# ButtonMatrix.net
KiCad netlist of a schematic drawn in EAGLE
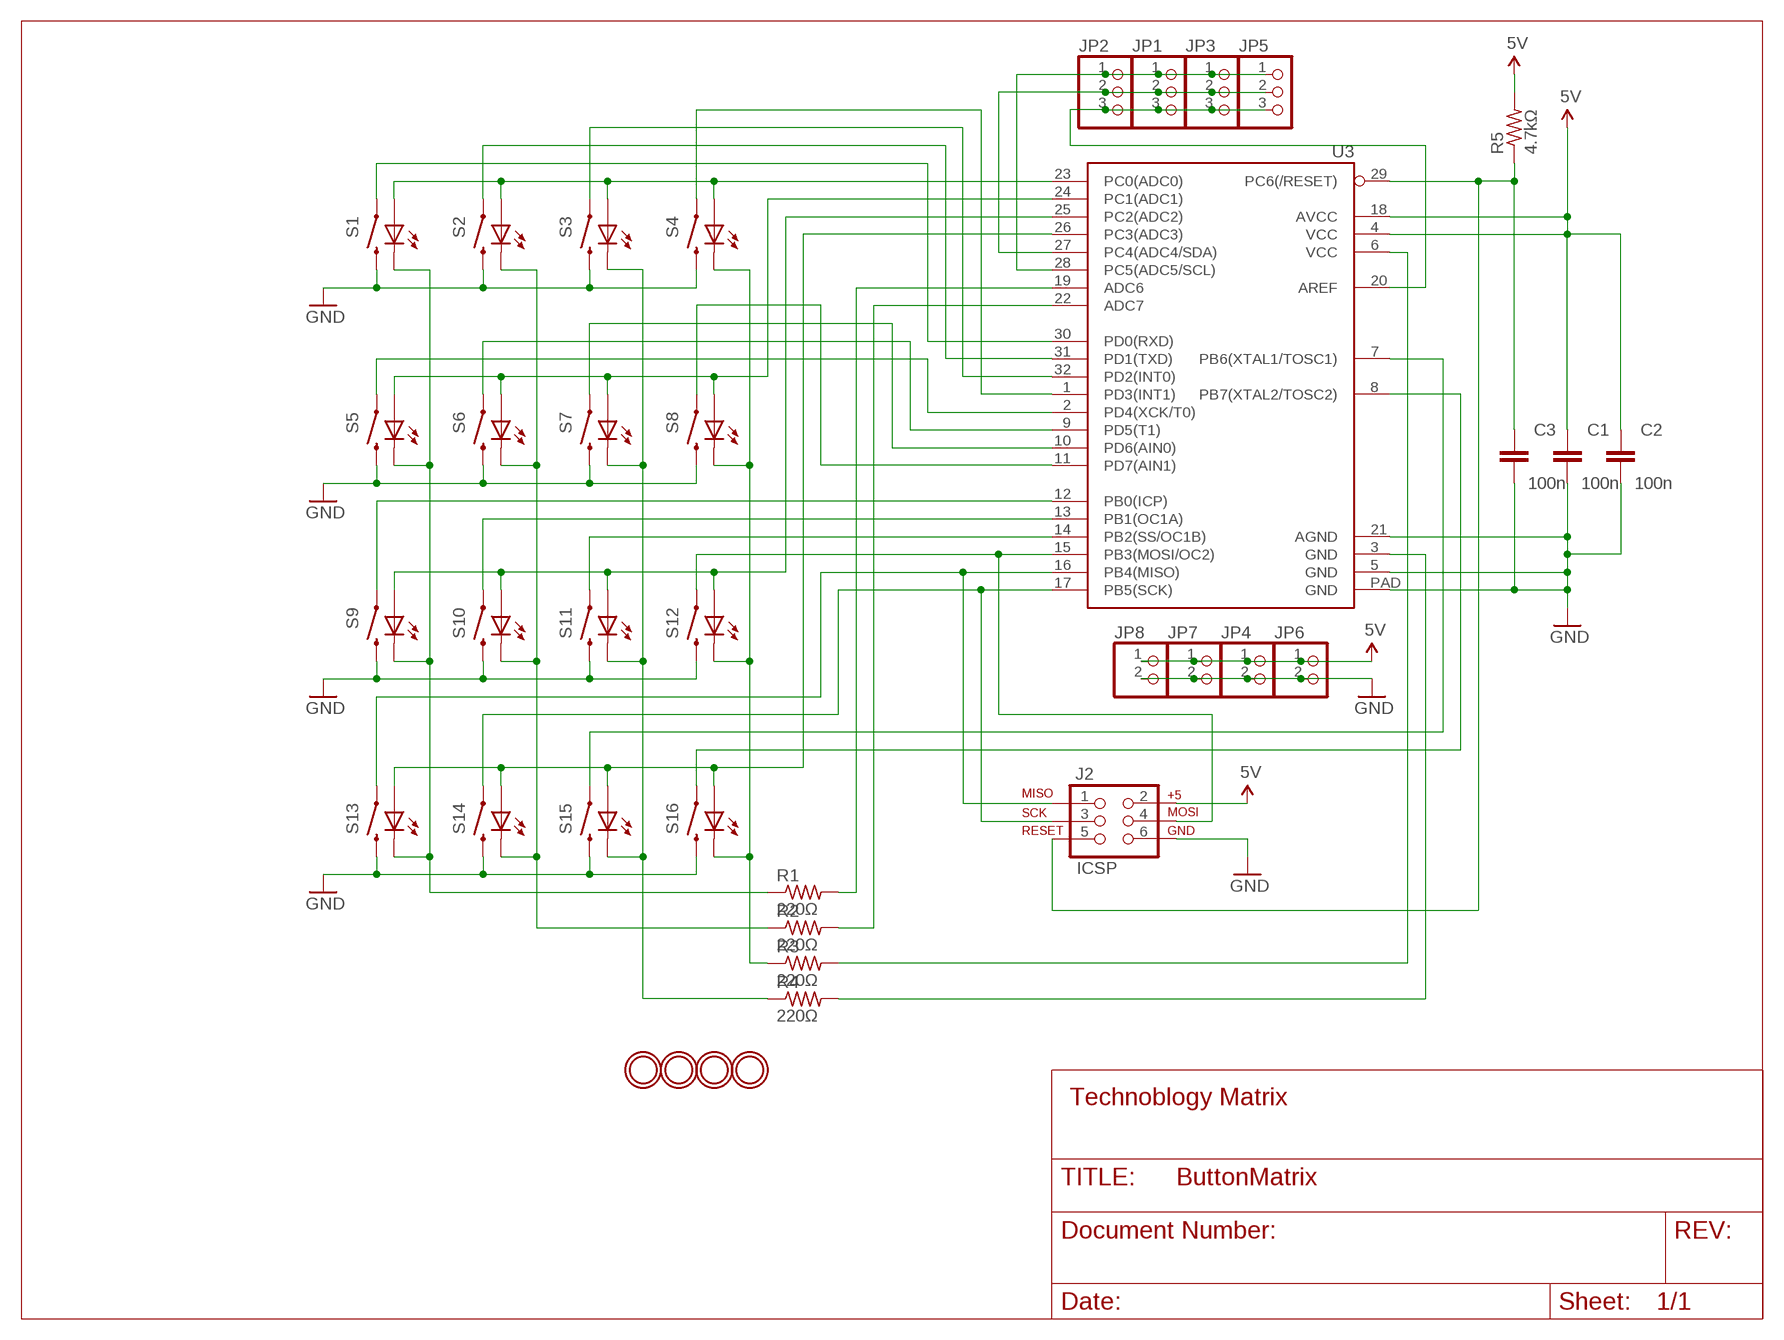
[diagram p0: schematic, sheet 1]

(export (version "E")
  (design (tool "Eeschema 10.0.6"))
  (components
    (comp (ref "C1")
      (value "100n")
      (footprint "eagle-import:0603-CAP")
      (libsource (lib "eagle-import") (part "CAP0603-CAP"))
    )
    (comp (ref "C2")
      (value "100n")
      (footprint "eagle-import:0603-CAP")
      (libsource (lib "eagle-import") (part "CAP0603-CAP"))
    )
    (comp (ref "C3")
      (value "100n")
      (footprint "eagle-import:0603-CAP")
      (libsource (lib "eagle-import") (part "CAP0603-CAP"))
    )
    (comp (ref "J2")
      (value "ICSP")
      (footprint "eagle-import:2X3")
      (libsource (lib "eagle-import") (part "AVR_SPI_PRG_6PTH"))
    )
    (comp (ref "JP1")
      (value "HEADER-1X3EDGESMT")
      (footprint "eagle-import:1X03_EDGESMT")
      (libsource (lib "eagle-import") (part "HEADER-1X3EDGESMT"))
    )
    (comp (ref "JP2")
      (value "HEADER-1X3EDGESMT")
      (footprint "eagle-import:1X03_EDGESMT")
      (libsource (lib "eagle-import") (part "HEADER-1X3EDGESMT"))
    )
    (comp (ref "JP3")
      (value "HEADER-1X3EDGESMT")
      (footprint "eagle-import:1X03_EDGESMT")
      (libsource (lib "eagle-import") (part "HEADER-1X3EDGESMT"))
    )
    (comp (ref "JP4")
      (value "HEADER-1X2EDGE")
      (footprint "eagle-import:1X02_EDGESMT")
      (libsource (lib "eagle-import") (part "HEADER-1X2EDGE"))
    )
    (comp (ref "JP5")
      (value "HEADER-1X3EDGESMT")
      (footprint "eagle-import:1X03_EDGESMT")
      (libsource (lib "eagle-import") (part "HEADER-1X3EDGESMT"))
    )
    (comp (ref "JP6")
      (value "HEADER-1X2EDGE")
      (footprint "eagle-import:1X02_EDGESMT")
      (libsource (lib "eagle-import") (part "HEADER-1X2EDGE"))
    )
    (comp (ref "JP7")
      (value "HEADER-1X2EDGE")
      (footprint "eagle-import:1X02_EDGESMT")
      (libsource (lib "eagle-import") (part "HEADER-1X2EDGE"))
    )
    (comp (ref "JP8")
      (value "HEADER-1X2EDGE")
      (footprint "eagle-import:1X02_EDGESMT")
      (libsource (lib "eagle-import") (part "HEADER-1X2EDGE"))
    )
    (comp (ref "R1")
      (value "220Ω")
      (footprint "eagle-import:R0805")
      (libsource (lib "eagle-import") (part "R-US_R0805"))
    )
    (comp (ref "R2")
      (value "220Ω")
      (footprint "eagle-import:R0805")
      (libsource (lib "eagle-import") (part "R-US_R0805"))
    )
    (comp (ref "R3")
      (value "220Ω")
      (footprint "eagle-import:R0805")
      (libsource (lib "eagle-import") (part "R-US_R0805"))
    )
    (comp (ref "R4")
      (value "220Ω")
      (footprint "eagle-import:R0805")
      (libsource (lib "eagle-import") (part "R-US_R0805"))
    )
    (comp (ref "R5")
      (value "4.7kΩ")
      (footprint "eagle-import:R0805")
      (libsource (lib "eagle-import") (part "R-US_R0805"))
    )
    (comp (ref "S1")
      (value "SWITCH-MOMENTARY-LEDPTH")
      (footprint "eagle-import:TACTILE-PTH-LED-12MM")
      (libsource (lib "eagle-import") (part "SWITCH-MOMENTARY-LEDPTH"))
    )
    (comp (ref "S2")
      (value "SWITCH-MOMENTARY-LEDPTH")
      (footprint "eagle-import:TACTILE-PTH-LED-12MM")
      (libsource (lib "eagle-import") (part "SWITCH-MOMENTARY-LEDPTH"))
    )
    (comp (ref "S3")
      (value "SWITCH-MOMENTARY-LEDPTH")
      (footprint "eagle-import:TACTILE-PTH-LED-12MM")
      (libsource (lib "eagle-import") (part "SWITCH-MOMENTARY-LEDPTH"))
    )
    (comp (ref "S4")
      (value "SWITCH-MOMENTARY-LEDPTH")
      (footprint "eagle-import:TACTILE-PTH-LED-12MM")
      (libsource (lib "eagle-import") (part "SWITCH-MOMENTARY-LEDPTH"))
    )
    (comp (ref "S5")
      (value "SWITCH-MOMENTARY-LEDPTH")
      (footprint "eagle-import:TACTILE-PTH-LED-12MM")
      (libsource (lib "eagle-import") (part "SWITCH-MOMENTARY-LEDPTH"))
    )
    (comp (ref "S6")
      (value "SWITCH-MOMENTARY-LEDPTH")
      (footprint "eagle-import:TACTILE-PTH-LED-12MM")
      (libsource (lib "eagle-import") (part "SWITCH-MOMENTARY-LEDPTH"))
    )
    (comp (ref "S7")
      (value "SWITCH-MOMENTARY-LEDPTH")
      (footprint "eagle-import:TACTILE-PTH-LED-12MM")
      (libsource (lib "eagle-import") (part "SWITCH-MOMENTARY-LEDPTH"))
    )
    (comp (ref "S8")
      (value "SWITCH-MOMENTARY-LEDPTH")
      (footprint "eagle-import:TACTILE-PTH-LED-12MM")
      (libsource (lib "eagle-import") (part "SWITCH-MOMENTARY-LEDPTH"))
    )
    (comp (ref "S9")
      (value "SWITCH-MOMENTARY-LEDPTH")
      (footprint "eagle-import:TACTILE-PTH-LED-12MM")
      (libsource (lib "eagle-import") (part "SWITCH-MOMENTARY-LEDPTH"))
    )
    (comp (ref "S10")
      (value "SWITCH-MOMENTARY-LEDPTH")
      (footprint "eagle-import:TACTILE-PTH-LED-12MM")
      (libsource (lib "eagle-import") (part "SWITCH-MOMENTARY-LEDPTH"))
    )
    (comp (ref "S11")
      (value "SWITCH-MOMENTARY-LEDPTH")
      (footprint "eagle-import:TACTILE-PTH-LED-12MM")
      (libsource (lib "eagle-import") (part "SWITCH-MOMENTARY-LEDPTH"))
    )
    (comp (ref "S12")
      (value "SWITCH-MOMENTARY-LEDPTH")
      (footprint "eagle-import:TACTILE-PTH-LED-12MM")
      (libsource (lib "eagle-import") (part "SWITCH-MOMENTARY-LEDPTH"))
    )
    (comp (ref "S13")
      (value "SWITCH-MOMENTARY-LEDPTH")
      (footprint "eagle-import:TACTILE-PTH-LED-12MM")
      (libsource (lib "eagle-import") (part "SWITCH-MOMENTARY-LEDPTH"))
    )
    (comp (ref "S14")
      (value "SWITCH-MOMENTARY-LEDPTH")
      (footprint "eagle-import:TACTILE-PTH-LED-12MM")
      (libsource (lib "eagle-import") (part "SWITCH-MOMENTARY-LEDPTH"))
    )
    (comp (ref "S15")
      (value "SWITCH-MOMENTARY-LEDPTH")
      (footprint "eagle-import:TACTILE-PTH-LED-12MM")
      (libsource (lib "eagle-import") (part "SWITCH-MOMENTARY-LEDPTH"))
    )
    (comp (ref "S16")
      (value "SWITCH-MOMENTARY-LEDPTH")
      (footprint "eagle-import:TACTILE-PTH-LED-12MM")
      (libsource (lib "eagle-import") (part "SWITCH-MOMENTARY-LEDPTH"))
    )
    (comp (ref "U$1")
      (value "MOUNTINGHOLE2.5")
      (footprint "eagle-import:MOUNTINGHOLE_2.5_PLATED")
      (libsource (lib "eagle-import") (part "MOUNTINGHOLE2.5"))
    )
    (comp (ref "U$2")
      (value "MOUNTINGHOLE2.5")
      (footprint "eagle-import:MOUNTINGHOLE_2.5_PLATED")
      (libsource (lib "eagle-import") (part "MOUNTINGHOLE2.5"))
    )
    (comp (ref "U$3")
      (value "MOUNTINGHOLE2.5")
      (footprint "eagle-import:MOUNTINGHOLE_2.5_PLATED")
      (libsource (lib "eagle-import") (part "MOUNTINGHOLE2.5"))
    )
    (comp (ref "U$4")
      (value "MOUNTINGHOLE2.5")
      (footprint "eagle-import:MOUNTINGHOLE_2.5_PLATED")
      (libsource (lib "eagle-import") (part "MOUNTINGHOLE2.5"))
    )
    (comp (ref "U3")
      (value "ATMEGA328P_MLFMLF32")
      (footprint "eagle-import:MLF32-PAD")
      (libsource (lib "eagle-import") (part "ATMEGA328P_MLFMLF32"))
    )
  )
  (nets
    (net (code "1") (name "5V") (class "Default")
      (node (ref "C1") (pin "1") (pinfunction "1_1") (pintype "passive"))
      (node (ref "C2") (pin "1") (pinfunction "1_1") (pintype "passive"))
      (node (ref "J2") (pin "2") (pinfunction "2_2") (pintype "passive"))
      (node (ref "JP4") (pin "1") (pinfunction "1_1") (pintype "passive"))
      (node (ref "JP6") (pin "1") (pinfunction "1_1") (pintype "passive"))
      (node (ref "JP7") (pin "1") (pinfunction "1_1") (pintype "passive"))
      (node (ref "JP8") (pin "1") (pinfunction "1_1") (pintype "passive"))
      (node (ref "R5") (pin "2") (pinfunction "2_2") (pintype "passive"))
      (node (ref "U3") (pin "18") (pinfunction "AVCC_18") (pintype "bidirectional"))
      (node (ref "U3") (pin "4") (pinfunction "VCC_4") (pintype "bidirectional"))
    )
    (net (code "2") (name "GND") (class "Default")
      (node (ref "C1") (pin "2") (pinfunction "2_2") (pintype "passive"))
      (node (ref "C2") (pin "2") (pinfunction "2_2") (pintype "passive"))
      (node (ref "C3") (pin "2") (pinfunction "2_2") (pintype "passive"))
      (node (ref "J2") (pin "6") (pinfunction "6_6") (pintype "passive"))
      (node (ref "JP4") (pin "2") (pinfunction "2_2") (pintype "passive"))
      (node (ref "JP6") (pin "2") (pinfunction "2_2") (pintype "passive"))
      (node (ref "JP7") (pin "2") (pinfunction "2_2") (pintype "passive"))
      (node (ref "JP8") (pin "2") (pinfunction "2_2") (pintype "passive"))
      (node (ref "S1") (pin "2") (pinfunction "2_2") (pintype "passive"))
      (node (ref "S10") (pin "2") (pinfunction "2_2") (pintype "passive"))
      (node (ref "S11") (pin "2") (pinfunction "2_2") (pintype "passive"))
      (node (ref "S12") (pin "2") (pinfunction "2_2") (pintype "passive"))
      (node (ref "S13") (pin "2") (pinfunction "2_2") (pintype "passive"))
      (node (ref "S14") (pin "2") (pinfunction "2_2") (pintype "passive"))
      (node (ref "S15") (pin "2") (pinfunction "2_2") (pintype "passive"))
      (node (ref "S16") (pin "2") (pinfunction "2_2") (pintype "passive"))
      (node (ref "S2") (pin "2") (pinfunction "2_2") (pintype "passive"))
      (node (ref "S3") (pin "2") (pinfunction "2_2") (pintype "passive"))
      (node (ref "S4") (pin "2") (pinfunction "2_2") (pintype "passive"))
      (node (ref "S5") (pin "2") (pinfunction "2_2") (pintype "passive"))
      (node (ref "S6") (pin "2") (pinfunction "2_2") (pintype "passive"))
      (node (ref "S7") (pin "2") (pinfunction "2_2") (pintype "passive"))
      (node (ref "S8") (pin "2") (pinfunction "2_2") (pintype "passive"))
      (node (ref "S9") (pin "2") (pinfunction "2_2") (pintype "passive"))
      (node (ref "U3") (pin "21") (pinfunction "AGND_21") (pintype "bidirectional"))
      (node (ref "U3") (pin "5") (pinfunction "GND_5") (pintype "bidirectional"))
      (node (ref "U3") (pin "PAD") (pinfunction "GND_PAD") (pintype "bidirectional"))
    )
    (net (code "3") (name "Net-(R1-Pad1)") (class "Default")
      (node (ref "R1") (pin "1") (pinfunction "1_1") (pintype "passive"))
      (node (ref "S1") (pin "C") (pinfunction "C_C") (pintype "passive"))
      (node (ref "S13") (pin "C") (pinfunction "C_C") (pintype "passive"))
      (node (ref "S5") (pin "C") (pinfunction "C_C") (pintype "passive"))
      (node (ref "S9") (pin "C") (pinfunction "C_C") (pintype "passive"))
    )
    (net (code "4") (name "Net-(R2-Pad1)") (class "Default")
      (node (ref "R2") (pin "1") (pinfunction "1_1") (pintype "passive"))
      (node (ref "S10") (pin "C") (pinfunction "C_C") (pintype "passive"))
      (node (ref "S14") (pin "C") (pinfunction "C_C") (pintype "passive"))
      (node (ref "S2") (pin "C") (pinfunction "C_C") (pintype "passive"))
      (node (ref "S6") (pin "C") (pinfunction "C_C") (pintype "passive"))
    )
    (net (code "5") (name "Net-(R3-Pad1)") (class "Default")
      (node (ref "R3") (pin "1") (pinfunction "1_1") (pintype "passive"))
      (node (ref "S12") (pin "C") (pinfunction "C_C") (pintype "passive"))
      (node (ref "S16") (pin "C") (pinfunction "C_C") (pintype "passive"))
      (node (ref "S4") (pin "C") (pinfunction "C_C") (pintype "passive"))
      (node (ref "S8") (pin "C") (pinfunction "C_C") (pintype "passive"))
    )
    (net (code "6") (name "Net-(R3-Pad2)") (class "Default")
      (node (ref "R3") (pin "2") (pinfunction "2_2") (pintype "passive"))
      (node (ref "U3") (pin "6") (pinfunction "VCC_6") (pintype "bidirectional"))
    )
    (net (code "7") (name "Net-(R4-Pad1)") (class "Default")
      (node (ref "R4") (pin "1") (pinfunction "1_1") (pintype "passive"))
      (node (ref "S11") (pin "C") (pinfunction "C_C") (pintype "passive"))
      (node (ref "S15") (pin "C") (pinfunction "C_C") (pintype "passive"))
      (node (ref "S3") (pin "C") (pinfunction "C_C") (pintype "passive"))
      (node (ref "S7") (pin "C") (pinfunction "C_C") (pintype "passive"))
    )
    (net (code "8") (name "Net-(R4-Pad2)") (class "Default")
      (node (ref "R4") (pin "2") (pinfunction "2_2") (pintype "passive"))
      (node (ref "U3") (pin "3") (pinfunction "GND_3") (pintype "bidirectional"))
    )
    (net (code "9") (name "Net-(S1-1)") (class "Default")
      (node (ref "S1") (pin "4") (pinfunction "1_4") (pintype "passive"))
      (node (ref "U3") (pin "30") (pinfunction "PD0(RXD)_30") (pintype "bidirectional"))
    )
    (net (code "10") (name "Net-(S2-1)") (class "Default")
      (node (ref "S2") (pin "4") (pinfunction "1_4") (pintype "passive"))
      (node (ref "U3") (pin "31") (pinfunction "PD1(TXD)_31") (pintype "bidirectional"))
    )
    (net (code "11") (name "Net-(S3-1)") (class "Default")
      (node (ref "S3") (pin "4") (pinfunction "1_4") (pintype "passive"))
      (node (ref "U3") (pin "32") (pinfunction "PD2(INT0)_32") (pintype "bidirectional"))
    )
    (net (code "12") (name "Net-(S4-1)") (class "Default")
      (node (ref "S4") (pin "4") (pinfunction "1_4") (pintype "passive"))
      (node (ref "U3") (pin "1") (pinfunction "PD3(INT1)_1") (pintype "bidirectional"))
    )
    (net (code "13") (name "Net-(S5-1)") (class "Default")
      (node (ref "S5") (pin "4") (pinfunction "1_4") (pintype "passive"))
      (node (ref "U3") (pin "2") (pinfunction "PD4(XCK/T0)_2") (pintype "bidirectional"))
    )
    (net (code "14") (name "Net-(S6-1)") (class "Default")
      (node (ref "S6") (pin "4") (pinfunction "1_4") (pintype "passive"))
      (node (ref "U3") (pin "9") (pinfunction "PD5(T1)_9") (pintype "bidirectional"))
    )
    (net (code "15") (name "Net-(S7-1)") (class "Default")
      (node (ref "S7") (pin "4") (pinfunction "1_4") (pintype "passive"))
      (node (ref "U3") (pin "10") (pinfunction "PD6(AIN0)_10") (pintype "bidirectional"))
    )
    (net (code "16") (name "Net-(S8-1)") (class "Default")
      (node (ref "S8") (pin "4") (pinfunction "1_4") (pintype "passive"))
      (node (ref "U3") (pin "11") (pinfunction "PD7(AIN1)_11") (pintype "bidirectional"))
    )
    (net (code "17") (name "Net-(S9-1)") (class "Default")
      (node (ref "S9") (pin "4") (pinfunction "1_4") (pintype "passive"))
      (node (ref "U3") (pin "12") (pinfunction "PB0(ICP)_12") (pintype "bidirectional"))
    )
    (net (code "18") (name "Net-(S10-1)") (class "Default")
      (node (ref "S10") (pin "4") (pinfunction "1_4") (pintype "passive"))
      (node (ref "U3") (pin "13") (pinfunction "PB1(OC1A)_13") (pintype "bidirectional"))
    )
    (net (code "19") (name "Net-(S11-1)") (class "Default")
      (node (ref "S11") (pin "4") (pinfunction "1_4") (pintype "passive"))
      (node (ref "U3") (pin "14") (pinfunction "PB2(SS/OC1B)_14") (pintype "bidirectional"))
    )
    (net (code "20") (name "Net-(S12-1)") (class "Default")
      (node (ref "J2") (pin "4") (pinfunction "4_4") (pintype "passive"))
      (node (ref "S12") (pin "4") (pinfunction "1_4") (pintype "passive"))
      (node (ref "U3") (pin "15") (pinfunction "PB3(MOSI/OC2)_15") (pintype "bidirectional"))
    )
    (net (code "21") (name "Net-(S13-1)") (class "Default")
      (node (ref "J2") (pin "1") (pinfunction "1_1") (pintype "passive"))
      (node (ref "S13") (pin "4") (pinfunction "1_4") (pintype "passive"))
      (node (ref "U3") (pin "16") (pinfunction "PB4(MISO)_16") (pintype "bidirectional"))
    )
    (net (code "22") (name "Net-(S14-1)") (class "Default")
      (node (ref "J2") (pin "3") (pinfunction "3_3") (pintype "passive"))
      (node (ref "S14") (pin "4") (pinfunction "1_4") (pintype "passive"))
      (node (ref "U3") (pin "17") (pinfunction "PB5(SCK)_17") (pintype "bidirectional"))
    )
    (net (code "23") (name "Net-(S15-1)") (class "Default")
      (node (ref "S15") (pin "4") (pinfunction "1_4") (pintype "passive"))
      (node (ref "U3") (pin "7") (pinfunction "PB6(XTAL1/TOSC1)_7") (pintype "bidirectional"))
    )
    (net (code "24") (name "Net-(S16-1)") (class "Default")
      (node (ref "S16") (pin "4") (pinfunction "1_4") (pintype "passive"))
      (node (ref "U3") (pin "8") (pinfunction "PB7(XTAL2/TOSC2)_8") (pintype "bidirectional"))
    )
    (net (code "25") (name "Net-(U3-ADC6)") (class "Default")
      (node (ref "R1") (pin "2") (pinfunction "2_2") (pintype "passive"))
      (node (ref "U3") (pin "19") (pinfunction "ADC6_19") (pintype "bidirectional"))
    )
    (net (code "26") (name "Net-(U3-ADC7)") (class "Default")
      (node (ref "R2") (pin "2") (pinfunction "2_2") (pintype "passive"))
      (node (ref "U3") (pin "22") (pinfunction "ADC7_22") (pintype "bidirectional"))
    )
    (net (code "27") (name "Net-(U3-AREF)") (class "Default")
      (node (ref "JP1") (pin "3") (pinfunction "3_3") (pintype "passive"))
      (node (ref "JP2") (pin "3") (pinfunction "3_3") (pintype "passive"))
      (node (ref "JP3") (pin "3") (pinfunction "3_3") (pintype "passive"))
      (node (ref "JP5") (pin "3") (pinfunction "3_3") (pintype "passive"))
      (node (ref "U3") (pin "20") (pinfunction "AREF_20") (pintype "bidirectional"))
    )
    (net (code "28") (name "Net-(U3-PC0(ADC0))") (class "Default")
      (node (ref "S1") (pin "A") (pinfunction "A_A") (pintype "passive"))
      (node (ref "S2") (pin "A") (pinfunction "A_A") (pintype "passive"))
      (node (ref "S3") (pin "A") (pinfunction "A_A") (pintype "passive"))
      (node (ref "S4") (pin "A") (pinfunction "A_A") (pintype "passive"))
      (node (ref "U3") (pin "23") (pinfunction "PC0(ADC0)_23") (pintype "bidirectional"))
    )
    (net (code "29") (name "Net-(U3-PC1(ADC1))") (class "Default")
      (node (ref "S5") (pin "A") (pinfunction "A_A") (pintype "passive"))
      (node (ref "S6") (pin "A") (pinfunction "A_A") (pintype "passive"))
      (node (ref "S7") (pin "A") (pinfunction "A_A") (pintype "passive"))
      (node (ref "S8") (pin "A") (pinfunction "A_A") (pintype "passive"))
      (node (ref "U3") (pin "24") (pinfunction "PC1(ADC1)_24") (pintype "bidirectional"))
    )
    (net (code "30") (name "Net-(U3-PC2(ADC2))") (class "Default")
      (node (ref "S10") (pin "A") (pinfunction "A_A") (pintype "passive"))
      (node (ref "S11") (pin "A") (pinfunction "A_A") (pintype "passive"))
      (node (ref "S12") (pin "A") (pinfunction "A_A") (pintype "passive"))
      (node (ref "S9") (pin "A") (pinfunction "A_A") (pintype "passive"))
      (node (ref "U3") (pin "25") (pinfunction "PC2(ADC2)_25") (pintype "bidirectional"))
    )
    (net (code "31") (name "Net-(U3-PC3(ADC3))") (class "Default")
      (node (ref "S13") (pin "A") (pinfunction "A_A") (pintype "passive"))
      (node (ref "S14") (pin "A") (pinfunction "A_A") (pintype "passive"))
      (node (ref "S15") (pin "A") (pinfunction "A_A") (pintype "passive"))
      (node (ref "S16") (pin "A") (pinfunction "A_A") (pintype "passive"))
      (node (ref "U3") (pin "26") (pinfunction "PC3(ADC3)_26") (pintype "bidirectional"))
    )
    (net (code "32") (name "Net-(U3-PC4(ADC4{slash}SDA))") (class "Default")
      (node (ref "JP1") (pin "2") (pinfunction "2_2") (pintype "passive"))
      (node (ref "JP2") (pin "2") (pinfunction "2_2") (pintype "passive"))
      (node (ref "JP3") (pin "2") (pinfunction "2_2") (pintype "passive"))
      (node (ref "JP5") (pin "2") (pinfunction "2_2") (pintype "passive"))
      (node (ref "U3") (pin "27") (pinfunction "PC4(ADC4/SDA)_27") (pintype "bidirectional"))
    )
    (net (code "33") (name "Net-(U3-PC5(ADC5{slash}SCL))") (class "Default")
      (node (ref "JP1") (pin "1") (pinfunction "1_1") (pintype "passive"))
      (node (ref "JP2") (pin "1") (pinfunction "1_1") (pintype "passive"))
      (node (ref "JP3") (pin "1") (pinfunction "1_1") (pintype "passive"))
      (node (ref "JP5") (pin "1") (pinfunction "1_1") (pintype "passive"))
      (node (ref "U3") (pin "28") (pinfunction "PC5(ADC5/SCL)_28") (pintype "bidirectional"))
    )
    (net (code "34") (name "Net-(U3-PC6({slash}RESET))") (class "Default")
      (node (ref "C3") (pin "1") (pinfunction "1_1") (pintype "passive"))
      (node (ref "J2") (pin "5") (pinfunction "5_5") (pintype "passive"))
      (node (ref "R5") (pin "1") (pinfunction "1_1") (pintype "passive"))
      (node (ref "U3") (pin "29") (pinfunction "PC6(/RESET)_29") (pintype "bidirectional"))
    )
  )
)
